# HnWrist_ExtendBoard.net
KiCad netlist of a schematic drawn in Altium Designer
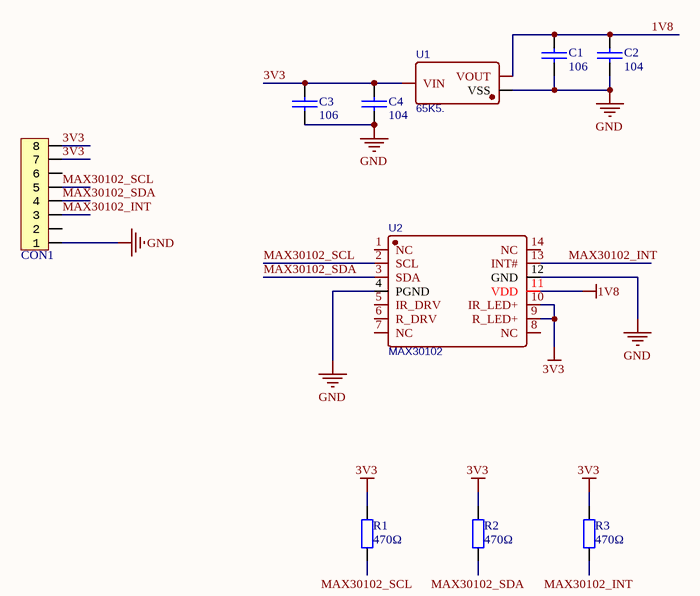
[diagram p0: HnWrist_ExtendBoard.SchDoc]

(export (version "E")
  (design (tool "Eeschema 10.0.6"))
  (components
    (comp (ref "C1")
      (value "106")
      (footprint "0603C")
      (description "无极性电容")
      (libsource (lib "MiniRacer") (part "CAP"))
    )
    (comp (ref "C2")
      (value "104")
      (footprint "0603C")
      (description "无极性电容")
      (libsource (lib "MiniRacer") (part "CAP"))
    )
    (comp (ref "C3")
      (value "106")
      (footprint "0603C")
      (description "无极性电容")
      (libsource (lib "MiniRacer") (part "CAP"))
    )
    (comp (ref "C4")
      (value "104")
      (footprint "0603C")
      (description "无极性电容")
      (libsource (lib "MiniRacer") (part "CAP"))
    )
    (comp (ref "CON1")
      (value "FFC_0.5_8")
      (footprint "FFC_0.5_8")
      (description "FFC")
      (libsource (lib "MainBoard") (part "FFC_0.5_8"))
    )
    (comp (ref "R1")
      (value "470Ω")
      (footprint "LC-0603_R")
      (description "贴片电阻")
      (libsource (lib "") (part "0603 470Ω (4700) 1%_1"))
    )
    (comp (ref "R2")
      (value "470Ω")
      (footprint "LC-0603_R")
      (description "贴片电阻")
      (libsource (lib "Miscellaneous Devices LC") (part "0603 470Ω (4700) 1%"))
    )
    (comp (ref "R3")
      (value "470Ω")
      (footprint "LC-0603_R")
      (description "贴片电阻")
      (libsource (lib "Miscellaneous Devices LC") (part "0603 470Ω (4700) 1%"))
    )
    (comp (ref "U1")
      (value "65K5.")
      (footprint "SOT-23-3_L2.9-W1.3-P1.90-LS2.4-BR")
      (fields (field (name "BOM_SUPPLIER PART") "C841299") (field (name "CONTRIBUTOR") "LCSC"))
      (libsource (lib "HnWrist_ExtendBoard") (part "65K5."))
    )
    (comp (ref "U2")
      (value "MAX30102")
      (footprint "SENSOR-SMD_MAX30102")
      (description "血氧心率芯片")
      (fields
        (field (name "BOM_MANUFACTURER PART") "MAX30100EFD+")
        (field (name "BOM_SUPPLIER PART") "C92512")
      )
      (libsource (lib "Chip") (part "MAX30102"))
    )
  )
  (nets
    (net (code "1") (name "/MAX30102_INT") (class "Default")
      (node (ref "CON1") (pin "3") (pinfunction "3_3") (pintype "passive"))
      (node (ref "R3") (pin "2") (pinfunction "2_2") (pintype "passive"))
      (node (ref "U2") (pin "13") (pinfunction "INT#_13") (pintype "passive"))
    )
    (net (code "2") (name "/MAX30102_SCL") (class "Default")
      (node (ref "CON1") (pin "5") (pinfunction "5_5") (pintype "passive"))
      (node (ref "R1") (pin "1") (pinfunction "1_1") (pintype "passive"))
      (node (ref "U2") (pin "2") (pinfunction "SCL_2") (pintype "passive"))
    )
    (net (code "3") (name "/MAX30102_SDA") (class "Default")
      (node (ref "CON1") (pin "4") (pinfunction "4_4") (pintype "passive"))
      (node (ref "R2") (pin "2") (pinfunction "2_2") (pintype "passive"))
      (node (ref "U2") (pin "3") (pinfunction "SDA_3") (pintype "passive"))
    )
    (net (code "4") (name "1V8") (class "Default")
      (node (ref "C1") (pin "2") (pinfunction "2_2") (pintype "passive"))
      (node (ref "C2") (pin "2") (pinfunction "2_2") (pintype "passive"))
      (node (ref "U1") (pin "2") (pinfunction "VOUT_2") (pintype "passive"))
      (node (ref "U2") (pin "11") (pinfunction "VDD_11") (pintype "passive"))
    )
    (net (code "5") (name "3V3") (class "Default")
      (node (ref "C3") (pin "2") (pinfunction "2_2") (pintype "passive"))
      (node (ref "C4") (pin "2") (pinfunction "2_2") (pintype "passive"))
      (node (ref "CON1") (pin "7") (pinfunction "7_7") (pintype "passive"))
      (node (ref "CON1") (pin "8") (pinfunction "8_8") (pintype "passive"))
      (node (ref "R1") (pin "2") (pinfunction "2_2") (pintype "passive"))
      (node (ref "R2") (pin "1") (pinfunction "1_1") (pintype "passive"))
      (node (ref "R3") (pin "1") (pinfunction "1_1") (pintype "passive"))
      (node (ref "U1") (pin "3") (pinfunction "VIN_3") (pintype "passive"))
      (node (ref "U2") (pin "10") (pinfunction "IR_LED+_10") (pintype "passive"))
      (node (ref "U2") (pin "9") (pinfunction "R_LED+_9") (pintype "passive"))
    )
    (net (code "6") (name "GND") (class "Default")
      (node (ref "C1") (pin "1") (pinfunction "1_1") (pintype "passive"))
      (node (ref "C2") (pin "1") (pinfunction "1_1") (pintype "passive"))
      (node (ref "C3") (pin "1") (pinfunction "1_1") (pintype "passive"))
      (node (ref "C4") (pin "1") (pinfunction "1_1") (pintype "passive"))
      (node (ref "CON1") (pin "1") (pinfunction "1_1") (pintype "passive"))
      (node (ref "U1") (pin "1") (pinfunction "VSS_1") (pintype "passive"))
      (node (ref "U2") (pin "12") (pinfunction "GND_12") (pintype "passive"))
      (node (ref "U2") (pin "4") (pinfunction "PGND_4") (pintype "passive"))
    )
    (net (code "7") (name "unconnected-(CON1-Pad2)") (class "Default")
      (node (ref "CON1") (pin "2") (pinfunction "2_2") (pintype "passive"))
    )
    (net (code "8") (name "unconnected-(CON1-Pad6)") (class "Default")
      (node (ref "CON1") (pin "6") (pinfunction "6_6") (pintype "passive"))
    )
    (net (code "9") (name "unconnected-(U2-IR_DRV-Pad5)") (class "Default")
      (node (ref "U2") (pin "5") (pinfunction "IR_DRV_5") (pintype "passive"))
    )
    (net (code "10") (name "unconnected-(U2-NC-Pad1)") (class "Default")
      (node (ref "U2") (pin "1") (pinfunction "NC_1") (pintype "passive"))
    )
    (net (code "11") (name "unconnected-(U2-NC-Pad7)") (class "Default")
      (node (ref "U2") (pin "7") (pinfunction "NC_7") (pintype "passive"))
    )
    (net (code "12") (name "unconnected-(U2-NC-Pad8)") (class "Default")
      (node (ref "U2") (pin "8") (pinfunction "NC_8") (pintype "passive"))
    )
    (net (code "13") (name "unconnected-(U2-NC-Pad14)") (class "Default")
      (node (ref "U2") (pin "14") (pinfunction "NC_14") (pintype "passive"))
    )
    (net (code "14") (name "unconnected-(U2-R_DRV-Pad6)") (class "Default")
      (node (ref "U2") (pin "6") (pinfunction "R_DRV_6") (pintype "passive"))
    )
  )
)
